# bluetoothle.net
KiCad netlist of a schematic drawn in Altium Designer
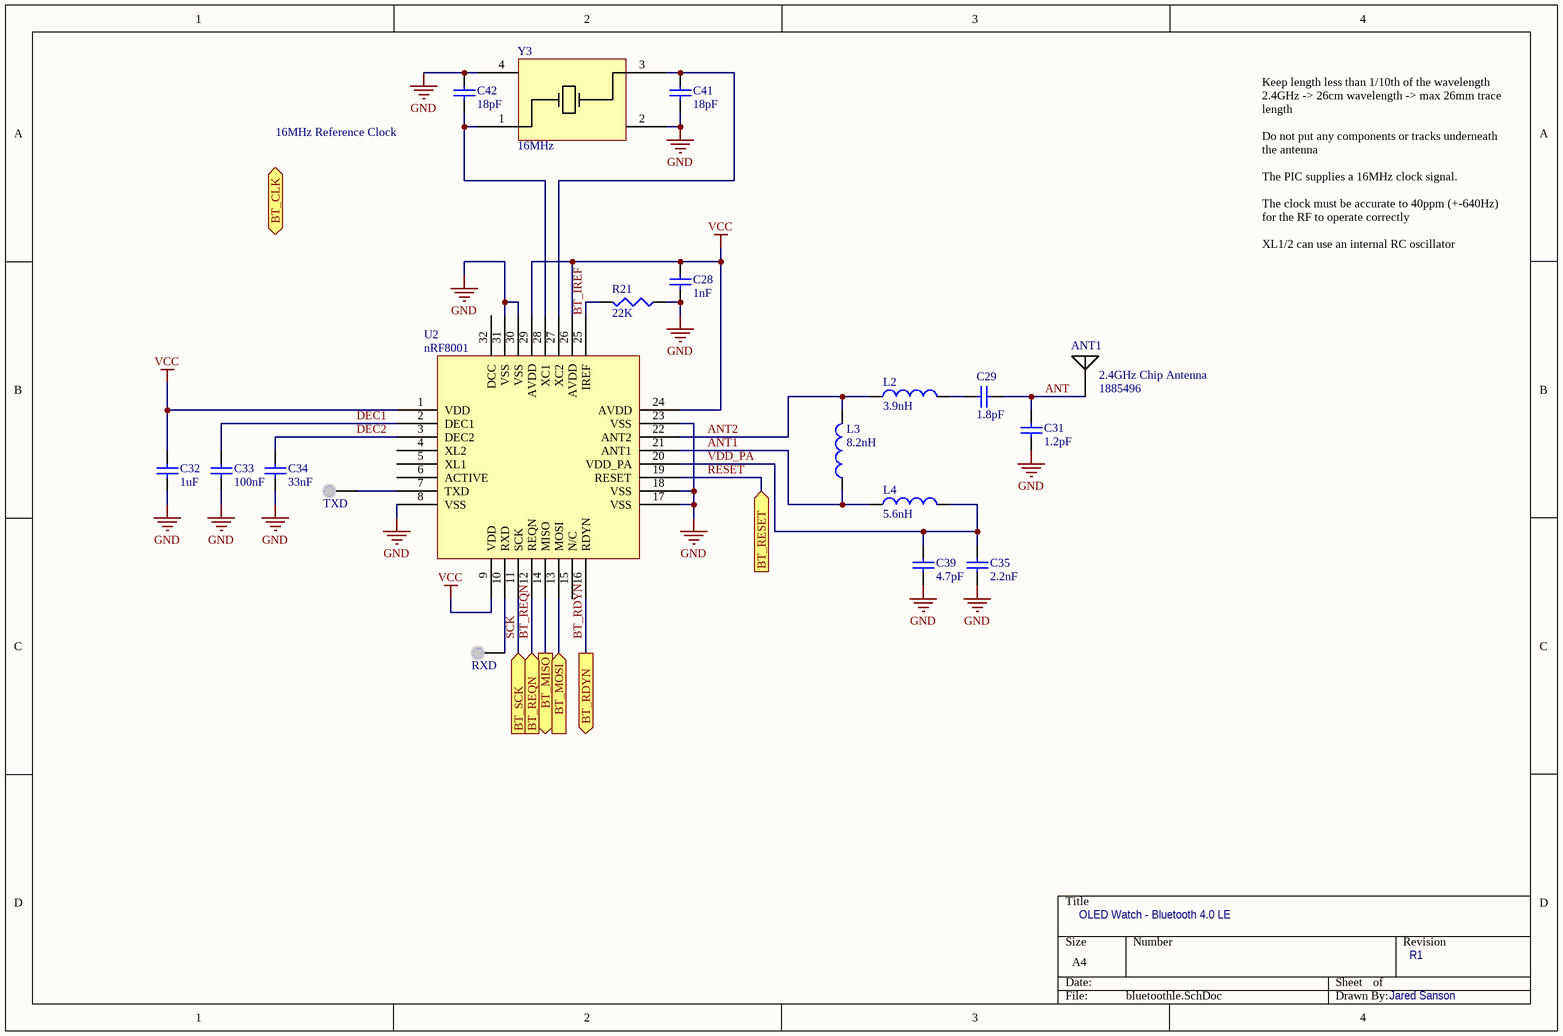
[diagram p0: bluetoothle.SchDoc]

(export (version "E")
  (design (tool "Eeschema 10.0.6"))
  (components
    (comp (ref "ANT1")
      (value "2.4GHz Chip Antenna")
      (footprint "2450AT18A100E")
      (description "JOHANSON TECHNOLOGY - 2450AT18A100E - ANTENNA, CERAMIC, 2.45GHZ")
      (fields
        (field (name "SUPPLIER PART NUMBER 1") "1885496")
        (field (name "MANUFACTURER") "JOHANSON TECHNOLOGY")
        (field (name "MANUFACTURER PART NUMBER") "2450AT18A100E")
      )
      (libsource (lib "JLib") (part "2450AT18A100E"))
    )
    (comp (ref "C28")
      (value "1nF")
      (footprint "0603C")
      (description "Capacitor")
      (fields (field (name "Comment") "Cap") (field (name "PUBLISHER") "Altium Limited"))
      (libsource (lib "Miscellaneous Devices") (part "Cap"))
    )
    (comp (ref "C29")
      (value "1.8pF")
      (footprint "0603C")
      (description "Capacitor")
      (fields (field (name "Comment") "Cap") (field (name "PUBLISHER") "Altium Limited"))
      (libsource (lib "Miscellaneous Devices") (part "Cap"))
    )
    (comp (ref "C31")
      (value "1.2pF")
      (footprint "0603C")
      (description "Capacitor")
      (fields (field (name "Comment") "Cap") (field (name "PUBLISHER") "Altium Limited"))
      (libsource (lib "Miscellaneous Devices") (part "Cap"))
    )
    (comp (ref "C32")
      (value "1uF")
      (footprint "0805C")
      (description "Capacitor")
      (fields (field (name "Comment") "Cap") (field (name "PUBLISHER") "Altium Limited"))
      (libsource (lib "Miscellaneous Devices") (part "Cap"))
    )
    (comp (ref "C33")
      (value "100nF")
      (footprint "0603C")
      (description "Capacitor")
      (fields (field (name "Comment") "Cap") (field (name "PUBLISHER") "Altium Limited"))
      (libsource (lib "Miscellaneous Devices") (part "Cap"))
    )
    (comp (ref "C34")
      (value "33nF")
      (footprint "0603C")
      (description "Capacitor")
      (fields (field (name "Comment") "Cap") (field (name "PUBLISHER") "Altium Limited"))
      (libsource (lib "Miscellaneous Devices") (part "Cap"))
    )
    (comp (ref "C35")
      (value "2.2nF")
      (footprint "0603C")
      (description "Capacitor")
      (fields (field (name "Comment") "Cap") (field (name "PUBLISHER") "Altium Limited"))
      (libsource (lib "Miscellaneous Devices") (part "Cap"))
    )
    (comp (ref "C39")
      (value "4.7pF")
      (footprint "0603C")
      (description "Capacitor")
      (fields (field (name "Comment") "Cap") (field (name "PUBLISHER") "Altium Limited"))
      (libsource (lib "Miscellaneous Devices") (part "Cap"))
    )
    (comp (ref "C41")
      (value "18pF")
      (footprint "0603C")
      (description "Capacitor")
      (fields (field (name "Comment") "Cap") (field (name "PUBLISHER") "Altium Limited"))
      (libsource (lib "Miscellaneous Devices") (part "Cap"))
    )
    (comp (ref "C42")
      (value "18pF")
      (footprint "0603C")
      (description "Capacitor")
      (fields (field (name "Comment") "Cap") (field (name "PUBLISHER") "Altium Limited"))
      (libsource (lib "Miscellaneous Devices") (part "Cap"))
    )
    (comp (ref "L2")
      (value "3.9nH")
      (footprint "0603L")
      (description "Inductor")
      (fields (field (name "PUBLISHER") "Altium Limited"))
      (libsource (lib "Miscellaneous Devices") (part "Inductor"))
    )
    (comp (ref "L3")
      (value "8.2nH")
      (footprint "0603L")
      (description "Inductor")
      (fields (field (name "PUBLISHER") "Altium Limited"))
      (libsource (lib "Miscellaneous Devices") (part "Inductor"))
    )
    (comp (ref "L4")
      (value "5.6nH")
      (footprint "0603L")
      (description "Inductor")
      (fields (field (name "PUBLISHER") "Altium Limited"))
      (libsource (lib "Miscellaneous Devices") (part "Inductor"))
    )
    (comp (ref "R21")
      (value "22K")
      (footprint "0603R")
      (description "Resistor")
      (fields (field (name "Comment") "Res3") (field (name "PUBLISHER") "Altium Limited"))
      (libsource (lib "Miscellaneous Devices") (part "Res3"))
    )
    (comp (ref "RXD")
      (value "AN4")
      (footprint "TESTPOINT_TOP")
      (description "Test Point")
      (libsource (lib "JLib") (part "TestPoint"))
    )
    (comp (ref "TXD")
      (value "AN4")
      (footprint "TESTPOINT_TOP")
      (description "Test Point")
      (libsource (lib "JLib") (part "TestPoint"))
    )
    (comp (ref "U2")
      (value "nRF8001")
      (footprint "QFN50P500X500-32V5N")
      (libsource (lib "JLib") (part "nRF8001"))
    )
    (comp (ref "Y3")
      (value "16MHz")
      (footprint "TXC-16MHZ")
      (fields (field (name "Comment") "TXC-16MHz"))
      (libsource (lib "JLib") (part "CrystalTXC"))
    )
  )
  (nets
    (net (code "1") (name "/ANT") (class "Default")
      (node (ref "ANT1") (pin "1") (pinfunction "1_1") (pintype "passive"))
      (node (ref "C29") (pin "2") (pinfunction "2_2") (pintype "passive"))
      (node (ref "C31") (pin "2") (pinfunction "2_2") (pintype "passive"))
    )
    (net (code "2") (name "/ANT1") (class "Default")
      (node (ref "L3") (pin "1") (pinfunction "1_1") (pintype "passive"))
      (node (ref "L4") (pin "1") (pinfunction "1_1") (pintype "passive"))
      (node (ref "U2") (pin "21") (pinfunction "ANT1_21") (pintype "passive"))
    )
    (net (code "3") (name "/ANT2") (class "Default")
      (node (ref "L2") (pin "1") (pinfunction "1_1") (pintype "passive"))
      (node (ref "L3") (pin "2") (pinfunction "2_2") (pintype "passive"))
      (node (ref "U2") (pin "22") (pinfunction "ANT2_22") (pintype "passive"))
    )
    (net (code "5") (name "/BT_IREF") (class "Default")
      (node (ref "R21") (pin "2") (pinfunction "2_2") (pintype "passive"))
      (node (ref "U2") (pin "25") (pinfunction "IREF_25") (pintype "passive"))
    )
    (net (code "6") (name "/BT_MISO") (class "Default")
      (node (ref "U2") (pin "14") (pinfunction "MISO_14") (pintype "passive"))
    )
    (net (code "7") (name "/BT_MOSI") (class "Default")
      (node (ref "U2") (pin "13") (pinfunction "MOSI_13") (pintype "passive"))
    )
    (net (code "8") (name "/BT_RDYN") (class "Default")
      (node (ref "U2") (pin "16") (pinfunction "RDYN_16") (pintype "passive"))
    )
    (net (code "9") (name "/BT_REQN") (class "Default")
      (node (ref "U2") (pin "12") (pinfunction "REQN_12") (pintype "passive"))
    )
    (net (code "10") (name "/DEC1") (class "Default")
      (node (ref "C33") (pin "1") (pinfunction "1_1") (pintype "passive"))
      (node (ref "U2") (pin "2") (pinfunction "DEC1_2") (pintype "passive"))
    )
    (net (code "11") (name "/DEC2") (class "Default")
      (node (ref "C34") (pin "1") (pinfunction "1_1") (pintype "passive"))
      (node (ref "U2") (pin "3") (pinfunction "DEC2_3") (pintype "passive"))
    )
    (net (code "12") (name "/RESET") (class "Default")
      (node (ref "U2") (pin "19") (pinfunction "RESET_19") (pintype "passive"))
    )
    (net (code "13") (name "/SCK") (class "Default")
      (node (ref "U2") (pin "11") (pinfunction "SCK_11") (pintype "passive"))
    )
    (net (code "14") (name "/VDD_PA") (class "Default")
      (node (ref "C35") (pin "1") (pinfunction "1_1") (pintype "passive"))
      (node (ref "C39") (pin "1") (pinfunction "1_1") (pintype "passive"))
      (node (ref "L4") (pin "2") (pinfunction "2_2") (pintype "passive"))
      (node (ref "U2") (pin "20") (pinfunction "VDD_PA_20") (pintype "passive"))
    )
    (net (code "15") (name "GND") (class "Default")
      (node (ref "C28") (pin "1") (pinfunction "1_1") (pintype "passive"))
      (node (ref "C31") (pin "1") (pinfunction "1_1") (pintype "passive"))
      (node (ref "C32") (pin "2") (pinfunction "2_2") (pintype "passive"))
      (node (ref "C33") (pin "2") (pinfunction "2_2") (pintype "passive"))
      (node (ref "C34") (pin "2") (pinfunction "2_2") (pintype "passive"))
      (node (ref "C35") (pin "2") (pinfunction "2_2") (pintype "passive"))
      (node (ref "C39") (pin "2") (pinfunction "2_2") (pintype "passive"))
      (node (ref "C41") (pin "1") (pinfunction "1_1") (pintype "passive"))
      (node (ref "C42") (pin "2") (pinfunction "2_2") (pintype "passive"))
      (node (ref "R21") (pin "1") (pinfunction "1_1") (pintype "passive"))
      (node (ref "U2") (pin "17") (pinfunction "VSS_17") (pintype "passive"))
      (node (ref "U2") (pin "18") (pinfunction "VSS_18") (pintype "passive"))
      (node (ref "U2") (pin "23") (pinfunction "VSS_23") (pintype "passive"))
      (node (ref "U2") (pin "30") (pinfunction "VSS_30") (pintype "passive"))
      (node (ref "U2") (pin "31") (pinfunction "VSS_31") (pintype "passive"))
      (node (ref "U2") (pin "8") (pinfunction "VSS_8") (pintype "passive"))
      (node (ref "Y3") (pin "2") (pinfunction "2_2") (pintype "passive"))
      (node (ref "Y3") (pin "4") (pinfunction "4_4") (pintype "passive"))
    )
    (net (code "16") (name "Net-(C29-Pad1)") (class "Default")
      (node (ref "C29") (pin "1") (pinfunction "1_1") (pintype "passive"))
      (node (ref "L2") (pin "2") (pinfunction "2_2") (pintype "passive"))
    )
    (net (code "17") (name "Net-(RXD-TP)") (class "Default")
      (node (ref "RXD") (pin "1") (pinfunction "TP_1") (pintype "passive"))
      (node (ref "U2") (pin "10") (pinfunction "RXD_10") (pintype "passive"))
    )
    (net (code "18") (name "Net-(TXD-TP)") (class "Default")
      (node (ref "TXD") (pin "1") (pinfunction "TP_1") (pintype "passive"))
      (node (ref "U2") (pin "7") (pinfunction "TXD_7") (pintype "passive"))
    )
    (net (code "19") (name "Net-(U2-XC1)") (class "Default")
      (node (ref "C42") (pin "1") (pinfunction "1_1") (pintype "passive"))
      (node (ref "U2") (pin "28") (pinfunction "XC1_28") (pintype "passive"))
      (node (ref "Y3") (pin "1") (pinfunction "1_1") (pintype "passive"))
    )
    (net (code "20") (name "Net-(U2-XC2)") (class "Default")
      (node (ref "C41") (pin "2") (pinfunction "2_2") (pintype "passive"))
      (node (ref "U2") (pin "27") (pinfunction "XC2_27") (pintype "passive"))
      (node (ref "Y3") (pin "3") (pinfunction "3_3") (pintype "passive"))
    )
    (net (code "21") (name "VCC") (class "Default")
      (node (ref "C28") (pin "2") (pinfunction "2_2") (pintype "passive"))
      (node (ref "C32") (pin "1") (pinfunction "1_1") (pintype "passive"))
      (node (ref "U2") (pin "1") (pinfunction "VDD_1") (pintype "passive"))
      (node (ref "U2") (pin "24") (pinfunction "AVDD_24") (pintype "passive"))
      (node (ref "U2") (pin "26") (pinfunction "AVDD_26") (pintype "passive"))
      (node (ref "U2") (pin "29") (pinfunction "AVDD_29") (pintype "passive"))
      (node (ref "U2") (pin "9") (pinfunction "VDD_9") (pintype "passive"))
    )
    (net (code "22") (name "unconnected-(U2-ACTIVE-Pad6)") (class "Default")
      (node (ref "U2") (pin "6") (pinfunction "ACTIVE_6") (pintype "passive"))
    )
    (net (code "23") (name "unconnected-(U2-DCC-Pad32)") (class "Default")
      (node (ref "U2") (pin "32") (pinfunction "DCC_32") (pintype "passive"))
    )
    (net (code "24") (name "unconnected-(U2-N{slash}C-Pad15)") (class "Default")
      (node (ref "U2") (pin "15") (pinfunction "N/C_15") (pintype "passive"))
    )
    (net (code "25") (name "unconnected-(U2-XL1-Pad5)") (class "Default")
      (node (ref "U2") (pin "5") (pinfunction "XL1_5") (pintype "passive"))
    )
    (net (code "26") (name "unconnected-(U2-XL2-Pad4)") (class "Default")
      (node (ref "U2") (pin "4") (pinfunction "XL2_4") (pintype "passive"))
    )
  )
)
